# top.net
KiCad netlist of a schematic drawn in Altium Designer
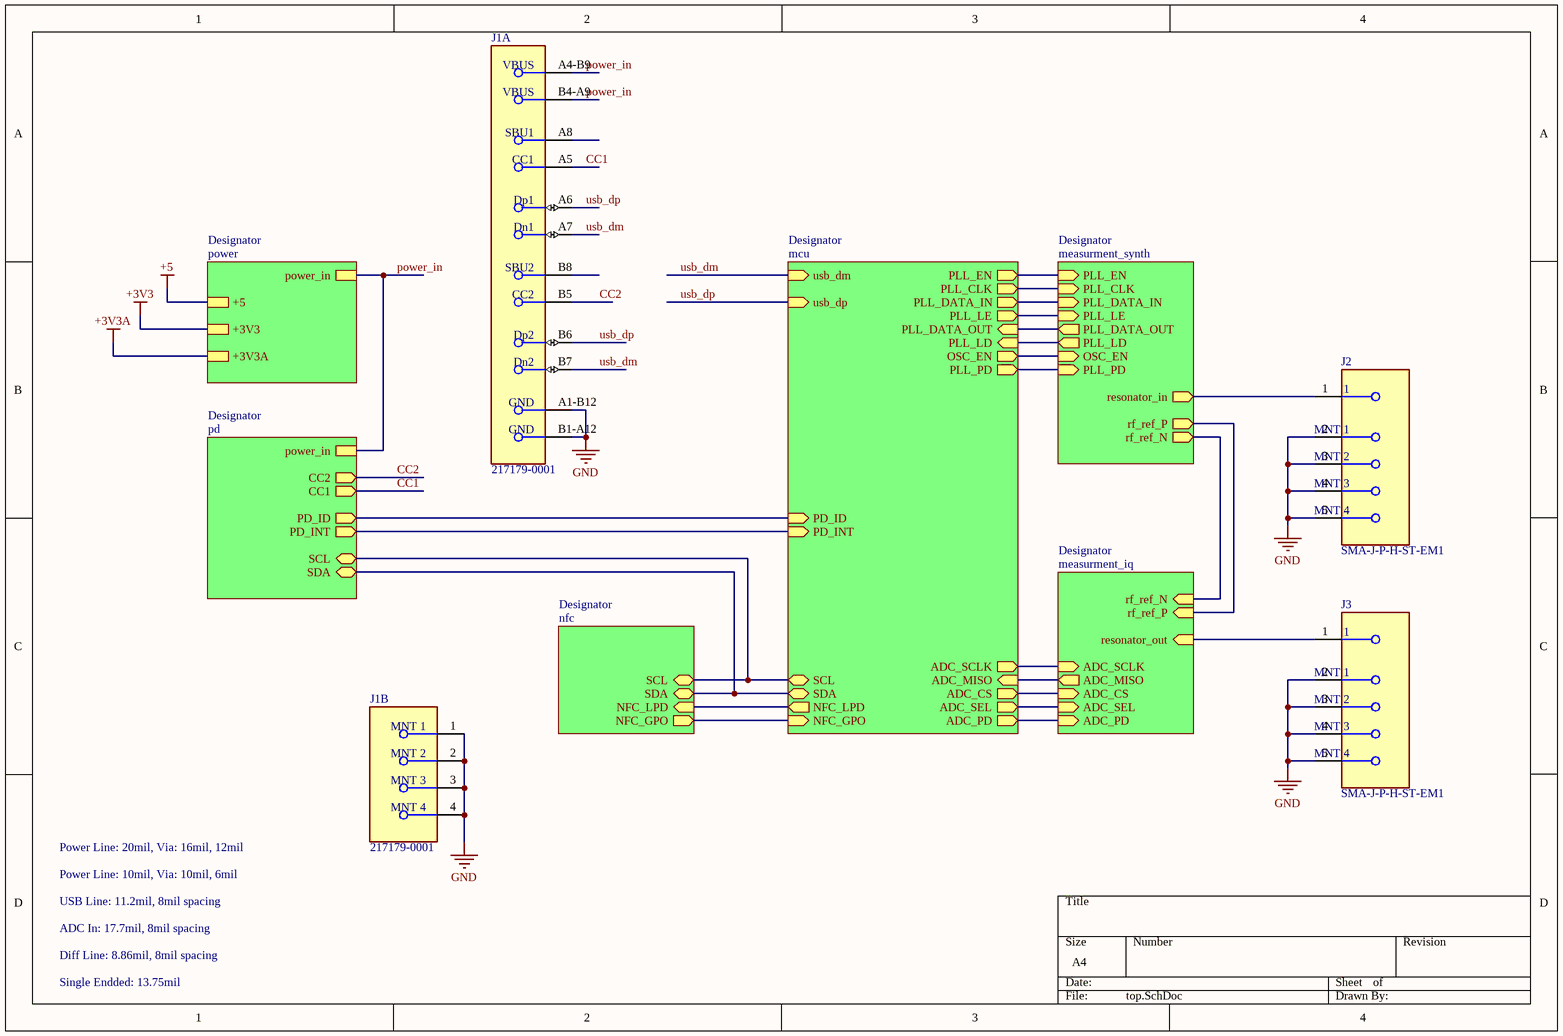
[diagram p0: top.SchDoc]

(export (version "E")
  (design (tool "Eeschema 10.0.6"))
  (components
    (comp (ref "J1")
      (value "217179-0001")
      (footprint "FP-2171790001-MFG")
      (description "CONN RCP USB2.0 TYP C 24P SMD RA")
      (libsource (lib "Altium Content Vault") (part "8b86497a633d14b3f74642136fc0ce6"))
    )
    (comp (ref "J2")
      (value "SMA-J-P-H-ST-EM1")
      (footprint "FP-SMA-J-P-H-ST-EM1-MFG")
      (description "CONN SMA JACK STR 50OHM EDGE MNT")
      (libsource (lib "Altium Content Vault") (part "c65b8a639cdaef1819ea20b5466f8fa"))
    )
    (comp (ref "J3")
      (value "SMA-J-P-H-ST-EM1")
      (footprint "FP-SMA-J-P-H-ST-EM1-MFG")
      (description "CONN SMA JACK STR 50OHM EDGE MNT")
      (libsource (lib "Altium Content Vault") (part "c65b8a639cdaef1819ea20b5466f8fa"))
    )
  )
  (nets
    (net (code "9") (name "/CC1") (class "Default")
      (node (ref "J1") (pin "A5") (pinfunction "CC1_A5") (pintype "passive"))
    )
    (net (code "10") (name "/CC2") (class "Default")
      (node (ref "J1") (pin "B5") (pinfunction "CC2_B5") (pintype "passive"))
    )
    (net (code "25") (name "/power_in") (class "Default")
      (node (ref "J1") (pin "A4-B9") (pinfunction "VBUS_A4-B9") (pintype "power_in"))
      (node (ref "J1") (pin "B4-A9") (pinfunction "VBUS_B4-A9") (pintype "power_in"))
    )
    (net (code "26") (name "/resonator_in") (class "Default")
      (node (ref "J2") (pin "1") (pinfunction "1_1") (pintype "passive"))
    )
    (net (code "27") (name "/resonator_out") (class "Default")
      (node (ref "J3") (pin "1") (pinfunction "1_1") (pintype "passive"))
    )
    (net (code "30") (name "/usb_dm") (class "Default")
      (node (ref "J1") (pin "A7") (pinfunction "Dn1_A7") (pintype "bidirectional"))
      (node (ref "J1") (pin "B7") (pinfunction "Dn2_B7") (pintype "bidirectional"))
    )
    (net (code "31") (name "/usb_dp") (class "Default")
      (node (ref "J1") (pin "A6") (pinfunction "Dp1_A6") (pintype "bidirectional"))
      (node (ref "J1") (pin "B6") (pinfunction "Dp2_B6") (pintype "bidirectional"))
    )
    (net (code "32") (name "GND") (class "Default")
      (node (ref "J1") (pin "1") (pinfunction "MNT_1_1") (pintype "passive"))
      (node (ref "J1") (pin "2") (pinfunction "MNT_2_2") (pintype "passive"))
      (node (ref "J1") (pin "3") (pinfunction "MNT_3_3") (pintype "power_in"))
      (node (ref "J1") (pin "4") (pinfunction "MNT_4_4") (pintype "power_in"))
      (node (ref "J1") (pin "A1-B12") (pinfunction "GND_A1-B12") (pintype "power_in"))
      (node (ref "J1") (pin "B1-A12") (pinfunction "GND_B1-A12") (pintype "power_in"))
      (node (ref "J2") (pin "2") (pinfunction "MNT_1_2") (pintype "passive"))
      (node (ref "J2") (pin "3") (pinfunction "MNT_2_3") (pintype "passive"))
      (node (ref "J2") (pin "4") (pinfunction "MNT_3_4") (pintype "passive"))
      (node (ref "J2") (pin "5") (pinfunction "MNT_4_5") (pintype "passive"))
      (node (ref "J3") (pin "2") (pinfunction "MNT_1_2") (pintype "passive"))
      (node (ref "J3") (pin "3") (pinfunction "MNT_2_3") (pintype "passive"))
      (node (ref "J3") (pin "4") (pinfunction "MNT_3_4") (pintype "passive"))
      (node (ref "J3") (pin "5") (pinfunction "MNT_4_5") (pintype "passive"))
    )
    (net (code "33") (name "unconnected-(J1A-SBU1-PadA8)") (class "Default")
      (node (ref "J1") (pin "A8") (pinfunction "SBU1_A8") (pintype "passive"))
    )
    (net (code "34") (name "unconnected-(J1A-SBU2-PadB8)") (class "Default")
      (node (ref "J1") (pin "B8") (pinfunction "SBU2_B8") (pintype "passive"))
    )
  )
)
